# ESP8266_Thermometer.net
KiCad netlist of a schematic drawn in EAGLE
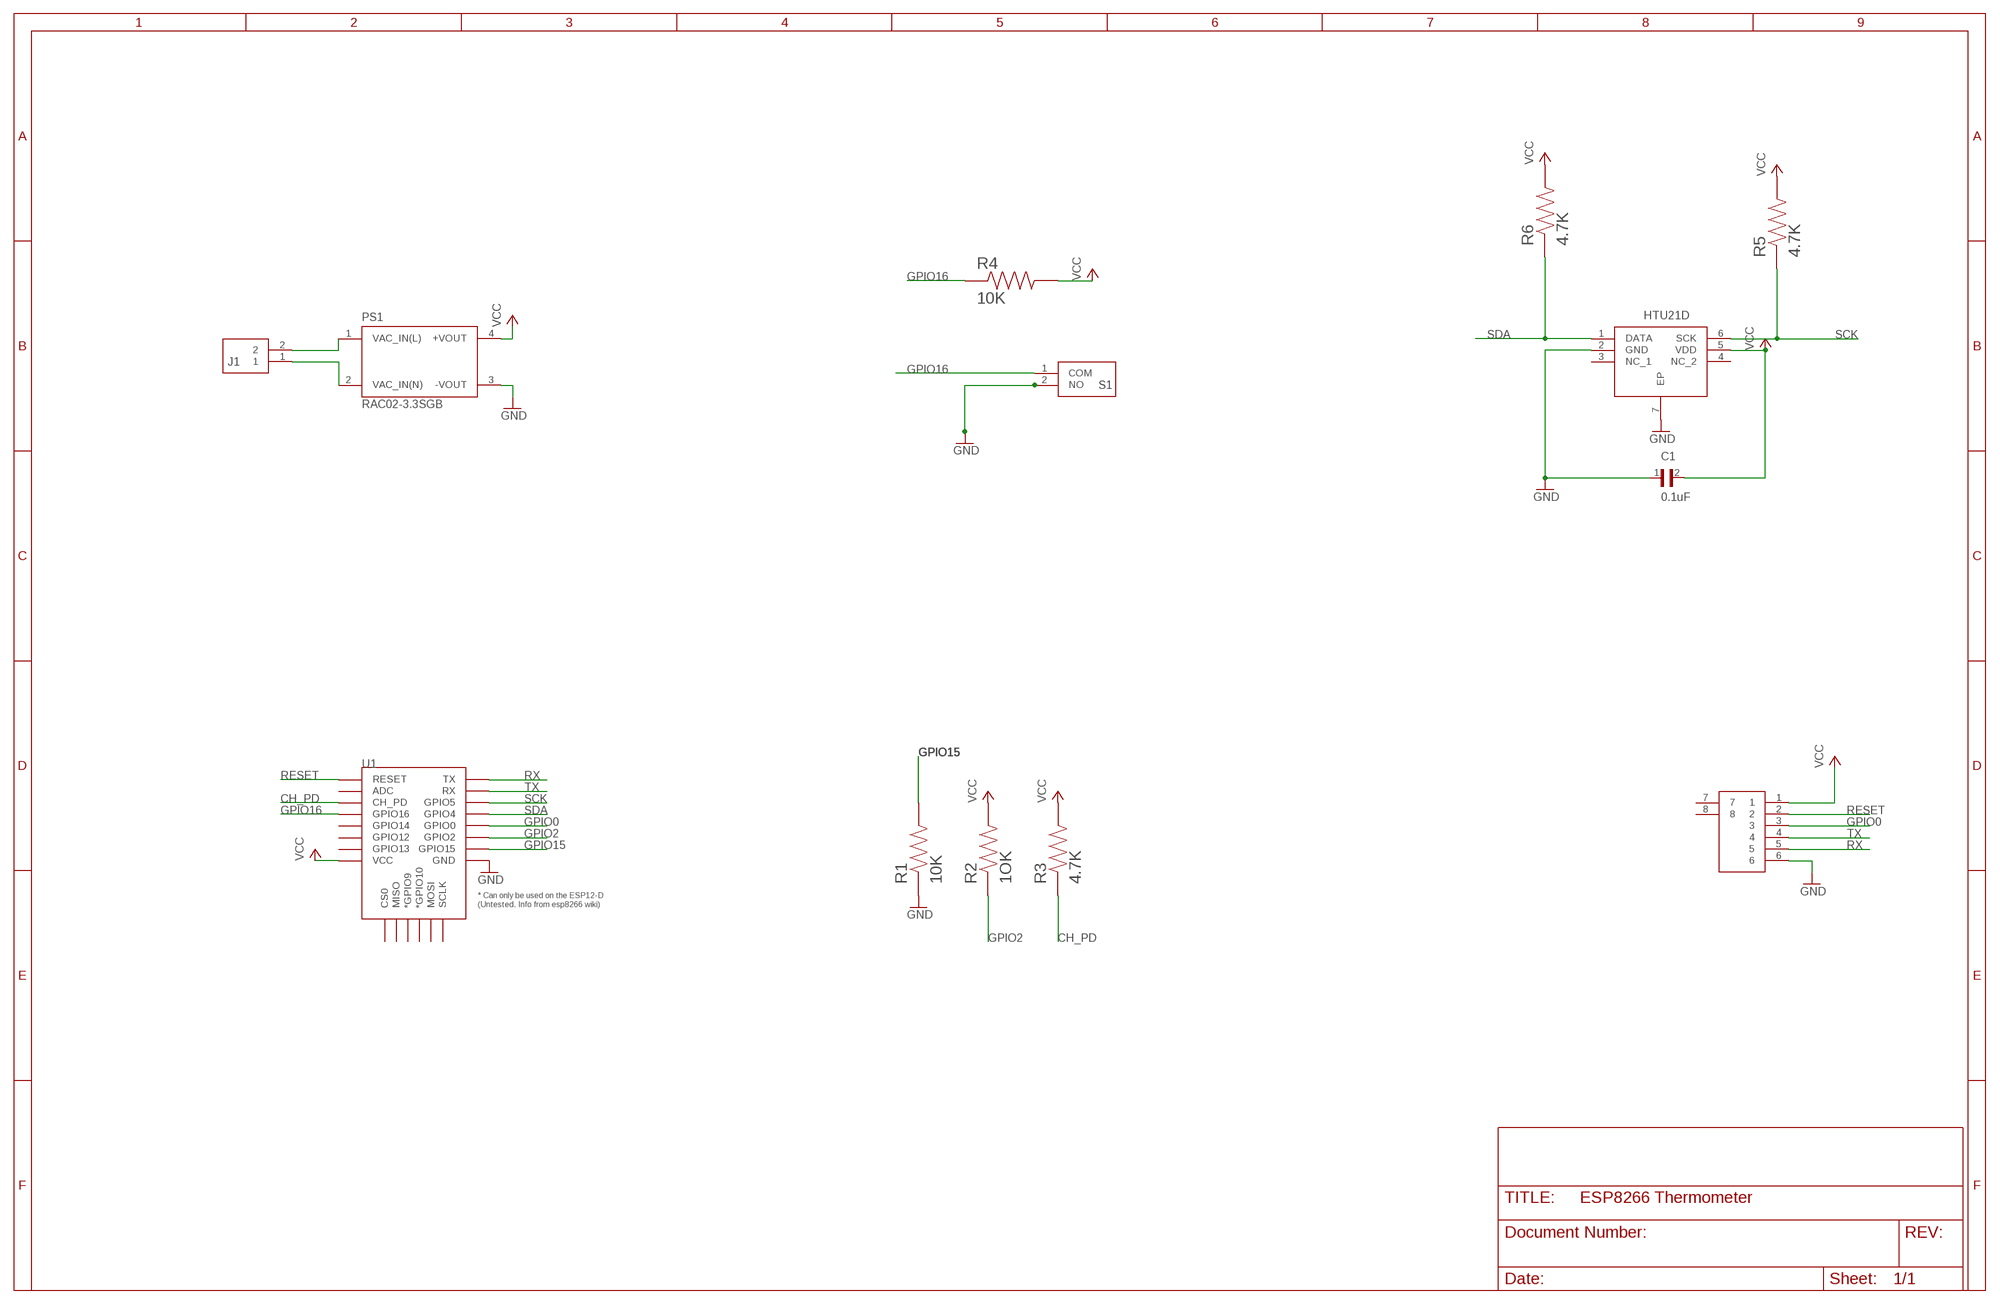
[diagram p0: schematic, sheet 1]

(export (version "E")
  (design (tool "Eeschema 10.0.6"))
  (components
    (comp (ref "C1")
      (value "0.1uF")
      (footprint "eagle-import:CAPC2012X94N")
      (fields (field (name "MF") "AVX") (field (name "MP") "0805YC103J4T2A"))
      (libsource (lib "eagle-import") (part "0805YC103J4T2A"))
    )
    (comp (ref "HM1")
      (value "HTU21D")
      (footprint "eagle-import:SON100P300X300X100-7N")
      (fields (field (name "MOUSER_PART_NUMBER") "824-HTU21D"))
      (libsource (lib "eagle-import") (part "HTU21D"))
    )
    (comp (ref "J1")
      (value "TB006-508-02BE")
      (footprint "eagle-import:TB00650802BE")
      (fields (field (name "MOUSER_PART_NUMBER") "490-TB006-508-02BE"))
      (libsource (lib "eagle-import") (part "TB006-508-02BE"))
    )
    (comp (ref "J2")
      (value "52852-0670")
      (footprint "eagle-import:528520670")
      (fields (field (name "MOUSER_PART_NUMBER") "538-52852-0670"))
      (libsource (lib "eagle-import") (part "52852-0670"))
    )
    (comp (ref "PS1")
      (value "RAC02-3.3SGB")
      (footprint "eagle-import:CONV_RAC02-3.3SGB")
      (fields (field (name "MF") "Recom Power"))
      (libsource (lib "eagle-import") (part "RAC02-3.3SGB"))
    )
    (comp (ref "R1")
      (value "10K")
      (footprint "eagle-import:RESC2012X60N")
      (fields (field (name "MF") "Yageo") (field (name "MP") "RC0805FR-07330RL"))
      (libsource (lib "eagle-import") (part "RC0805FR-07330RL"))
    )
    (comp (ref "R2")
      (value "1OK")
      (footprint "eagle-import:RESC2012X60N")
      (fields (field (name "MF") "Yageo") (field (name "MP") "RC0805FR-07330RL"))
      (libsource (lib "eagle-import") (part "RC0805FR-07330RL"))
    )
    (comp (ref "R3")
      (value "4.7K")
      (footprint "eagle-import:RESC2012X60N")
      (fields (field (name "MF") "Yageo") (field (name "MP") "RC0805FR-07330RL"))
      (libsource (lib "eagle-import") (part "RC0805FR-07330RL"))
    )
    (comp (ref "R4")
      (value "10K")
      (footprint "eagle-import:RESC2012X60N")
      (fields (field (name "MF") "Yageo") (field (name "MP") "RC0805FR-07330RL"))
      (libsource (lib "eagle-import") (part "RC0805FR-07330RL"))
    )
    (comp (ref "R5")
      (value "4.7K")
      (footprint "eagle-import:RESC2012X60N")
      (fields (field (name "MF") "Yageo") (field (name "MP") "RC0805FR-07330RL"))
      (libsource (lib "eagle-import") (part "RC0805FR-07330RL"))
    )
    (comp (ref "R6")
      (value "4.7K")
      (footprint "eagle-import:RESC2012X60N")
      (fields (field (name "MF") "Yageo") (field (name "MP") "RC0805FR-07330RL"))
      (libsource (lib "eagle-import") (part "RC0805FR-07330RL"))
    )
    (comp (ref "S1")
      (value "PTS636_SP50_SMTR_LFS")
      (footprint "eagle-import:PTS636SP50SMTRLFS")
      (fields
        (field (name "MANUFACTURER_PART_NUMBER") "PTS636 SP50 SMTR LFS")
        (field (name "MOUSER_PART_NUMBER") "611-PTS636SP50SMTRLF")
      )
      (libsource (lib "eagle-import") (part "PTS636_SP50_SMTR_LFS"))
    )
    (comp (ref "U1")
      (value "ESP12ESMD")
      (footprint "eagle-import:ESP12E-SMD")
      (libsource (lib "eagle-import") (part "ESP12ESMD"))
    )
  )
  (nets
    (net (code "1") (name "/CH_PD") (class "Default")
      (node (ref "R3") (pin "1") (pinfunction "1_1") (pintype "passive"))
      (node (ref "U1") (pin "CH_PD") (pinfunction "CH_PD_CH_PD") (pintype "bidirectional"))
    )
    (net (code "2") (name "/GPIO0") (class "Default")
      (node (ref "J2") (pin "3") (pinfunction "3_3") (pintype "bidirectional"))
      (node (ref "U1") (pin "GPIO0") (pinfunction "GPIO0_GPIO0") (pintype "bidirectional"))
    )
    (net (code "3") (name "/GPIO2") (class "Default")
      (node (ref "R2") (pin "1") (pinfunction "1_1") (pintype "passive"))
      (node (ref "U1") (pin "GPIO2") (pinfunction "GPIO2_GPIO2") (pintype "bidirectional"))
    )
    (net (code "4") (name "/GPIO15") (class "Default")
      (node (ref "R1") (pin "2") (pinfunction "2_2") (pintype "passive"))
      (node (ref "U1") (pin "GPIO15") (pinfunction "GPIO15_GPIO15") (pintype "bidirectional"))
    )
    (net (code "5") (name "/GPIO16") (class "Default")
      (node (ref "R4") (pin "1") (pinfunction "1_1") (pintype "passive"))
      (node (ref "S1") (pin "1") (pinfunction "COM_1") (pintype "bidirectional"))
      (node (ref "U1") (pin "GPIO16") (pinfunction "GPIO16_GPIO16") (pintype "bidirectional"))
    )
    (net (code "6") (name "/RESET") (class "Default")
      (node (ref "J2") (pin "2") (pinfunction "2_2") (pintype "bidirectional"))
      (node (ref "U1") (pin "RESET") (pinfunction "RESET_RESET") (pintype "bidirectional"))
    )
    (net (code "7") (name "/RX") (class "Default")
      (node (ref "J2") (pin "5") (pinfunction "5_5") (pintype "bidirectional"))
      (node (ref "U1") (pin "TXD0") (pinfunction "TX_TXD0") (pintype "bidirectional"))
    )
    (net (code "8") (name "/SCK") (class "Default")
      (node (ref "HM1") (pin "6") (pinfunction "SCK_6") (pintype "bidirectional"))
      (node (ref "R5") (pin "1") (pinfunction "1_1") (pintype "passive"))
      (node (ref "U1") (pin "GPIO5") (pinfunction "GPIO5_GPIO5") (pintype "bidirectional"))
    )
    (net (code "9") (name "/SDA") (class "Default")
      (node (ref "HM1") (pin "1") (pinfunction "DATA_1") (pintype "bidirectional"))
      (node (ref "R6") (pin "1") (pinfunction "1_1") (pintype "passive"))
      (node (ref "U1") (pin "GPIO4") (pinfunction "GPIO4_GPIO4") (pintype "bidirectional"))
    )
    (net (code "10") (name "/TX") (class "Default")
      (node (ref "J2") (pin "4") (pinfunction "4_4") (pintype "bidirectional"))
      (node (ref "U1") (pin "RXD0") (pinfunction "RX_RXD0") (pintype "bidirectional"))
    )
    (net (code "11") (name "GND") (class "Default")
      (node (ref "C1") (pin "1") (pinfunction "1_1") (pintype "passive"))
      (node (ref "HM1") (pin "2") (pinfunction "GND_2") (pintype "bidirectional"))
      (node (ref "HM1") (pin "7") (pinfunction "EP_7") (pintype "bidirectional"))
      (node (ref "J2") (pin "6") (pinfunction "6_6") (pintype "bidirectional"))
      (node (ref "PS1") (pin "3") (pinfunction "-VOUT_3") (pintype "output"))
      (node (ref "R1") (pin "1") (pinfunction "1_1") (pintype "passive"))
      (node (ref "S1") (pin "2") (pinfunction "NO_2") (pintype "bidirectional"))
      (node (ref "U1") (pin "GND") (pinfunction "GND_GND") (pintype "bidirectional"))
    )
    (net (code "12") (name "Net-(PS1-VAC_IN(L))") (class "Default")
      (node (ref "J1") (pin "2") (pinfunction "2_2") (pintype "bidirectional"))
      (node (ref "PS1") (pin "1") (pinfunction "VAC_IN(L)_1") (pintype "input"))
    )
    (net (code "13") (name "Net-(PS1-VAC_IN(N))") (class "Default")
      (node (ref "J1") (pin "1") (pinfunction "1_1") (pintype "bidirectional"))
      (node (ref "PS1") (pin "2") (pinfunction "VAC_IN(N)_2") (pintype "input"))
    )
    (net (code "14") (name "VCC") (class "Default")
      (node (ref "C1") (pin "2") (pinfunction "2_2") (pintype "passive"))
      (node (ref "HM1") (pin "5") (pinfunction "VDD_5") (pintype "bidirectional"))
      (node (ref "J2") (pin "1") (pinfunction "1_1") (pintype "bidirectional"))
      (node (ref "PS1") (pin "4") (pinfunction "+VOUT_4") (pintype "output"))
      (node (ref "R2") (pin "2") (pinfunction "2_2") (pintype "passive"))
      (node (ref "R3") (pin "2") (pinfunction "2_2") (pintype "passive"))
      (node (ref "R4") (pin "2") (pinfunction "2_2") (pintype "passive"))
      (node (ref "R5") (pin "2") (pinfunction "2_2") (pintype "passive"))
      (node (ref "R6") (pin "2") (pinfunction "2_2") (pintype "passive"))
      (node (ref "U1") (pin "VCC") (pinfunction "VCC_VCC") (pintype "bidirectional"))
    )
    (net (code "15") (name "unconnected-(HM1-NC_1-Pad3)") (class "Default")
      (node (ref "HM1") (pin "3") (pinfunction "NC_1_3") (pintype "bidirectional"))
    )
    (net (code "16") (name "unconnected-(HM1-NC_2-Pad4)") (class "Default")
      (node (ref "HM1") (pin "4") (pinfunction "NC_2_4") (pintype "bidirectional"))
    )
    (net (code "17") (name "unconnected-(J2-Pad7)") (class "Default")
      (node (ref "J2") (pin "7") (pinfunction "7_7") (pintype "bidirectional"))
    )
    (net (code "18") (name "unconnected-(J2-Pad8)") (class "Default")
      (node (ref "J2") (pin "8") (pinfunction "8_8") (pintype "bidirectional"))
    )
    (net (code "19") (name "unconnected-(U1-*GPIO9-PadGPIO9)") (class "Default")
      (node (ref "U1") (pin "GPIO9") (pinfunction "*GPIO9_GPIO9") (pintype "bidirectional"))
    )
    (net (code "20") (name "unconnected-(U1-*GPIO10-PadGPIO10)") (class "Default")
      (node (ref "U1") (pin "GPIO10") (pinfunction "*GPIO10_GPIO10") (pintype "bidirectional"))
    )
    (net (code "21") (name "unconnected-(U1-PadADC)") (class "Default")
      (node (ref "U1") (pin "ADC") (pinfunction "ADC_ADC") (pintype "bidirectional"))
    )
    (net (code "22") (name "unconnected-(U1-PadCS0)") (class "Default")
      (node (ref "U1") (pin "CS0") (pinfunction "CS0_CS0") (pintype "bidirectional"))
    )
    (net (code "23") (name "unconnected-(U1-PadGPIO12)") (class "Default")
      (node (ref "U1") (pin "GPIO12") (pinfunction "GPIO12_GPIO12") (pintype "bidirectional"))
    )
    (net (code "24") (name "unconnected-(U1-PadGPIO13)") (class "Default")
      (node (ref "U1") (pin "GPIO13") (pinfunction "GPIO13_GPIO13") (pintype "bidirectional"))
    )
    (net (code "25") (name "unconnected-(U1-PadGPIO14)") (class "Default")
      (node (ref "U1") (pin "GPIO14") (pinfunction "GPIO14_GPIO14") (pintype "bidirectional"))
    )
    (net (code "26") (name "unconnected-(U1-PadMISO)") (class "Default")
      (node (ref "U1") (pin "MISO") (pinfunction "MISO_MISO") (pintype "bidirectional"))
    )
    (net (code "27") (name "unconnected-(U1-PadMOSI)") (class "Default")
      (node (ref "U1") (pin "MOSI") (pinfunction "MOSI_MOSI") (pintype "bidirectional"))
    )
    (net (code "28") (name "unconnected-(U1-PadSCLK)") (class "Default")
      (node (ref "U1") (pin "SCLK") (pinfunction "SCLK_SCLK") (pintype "bidirectional"))
    )
  )
)
